# hv80_carrier.net
KiCad netlist of a schematic drawn in EAGLE
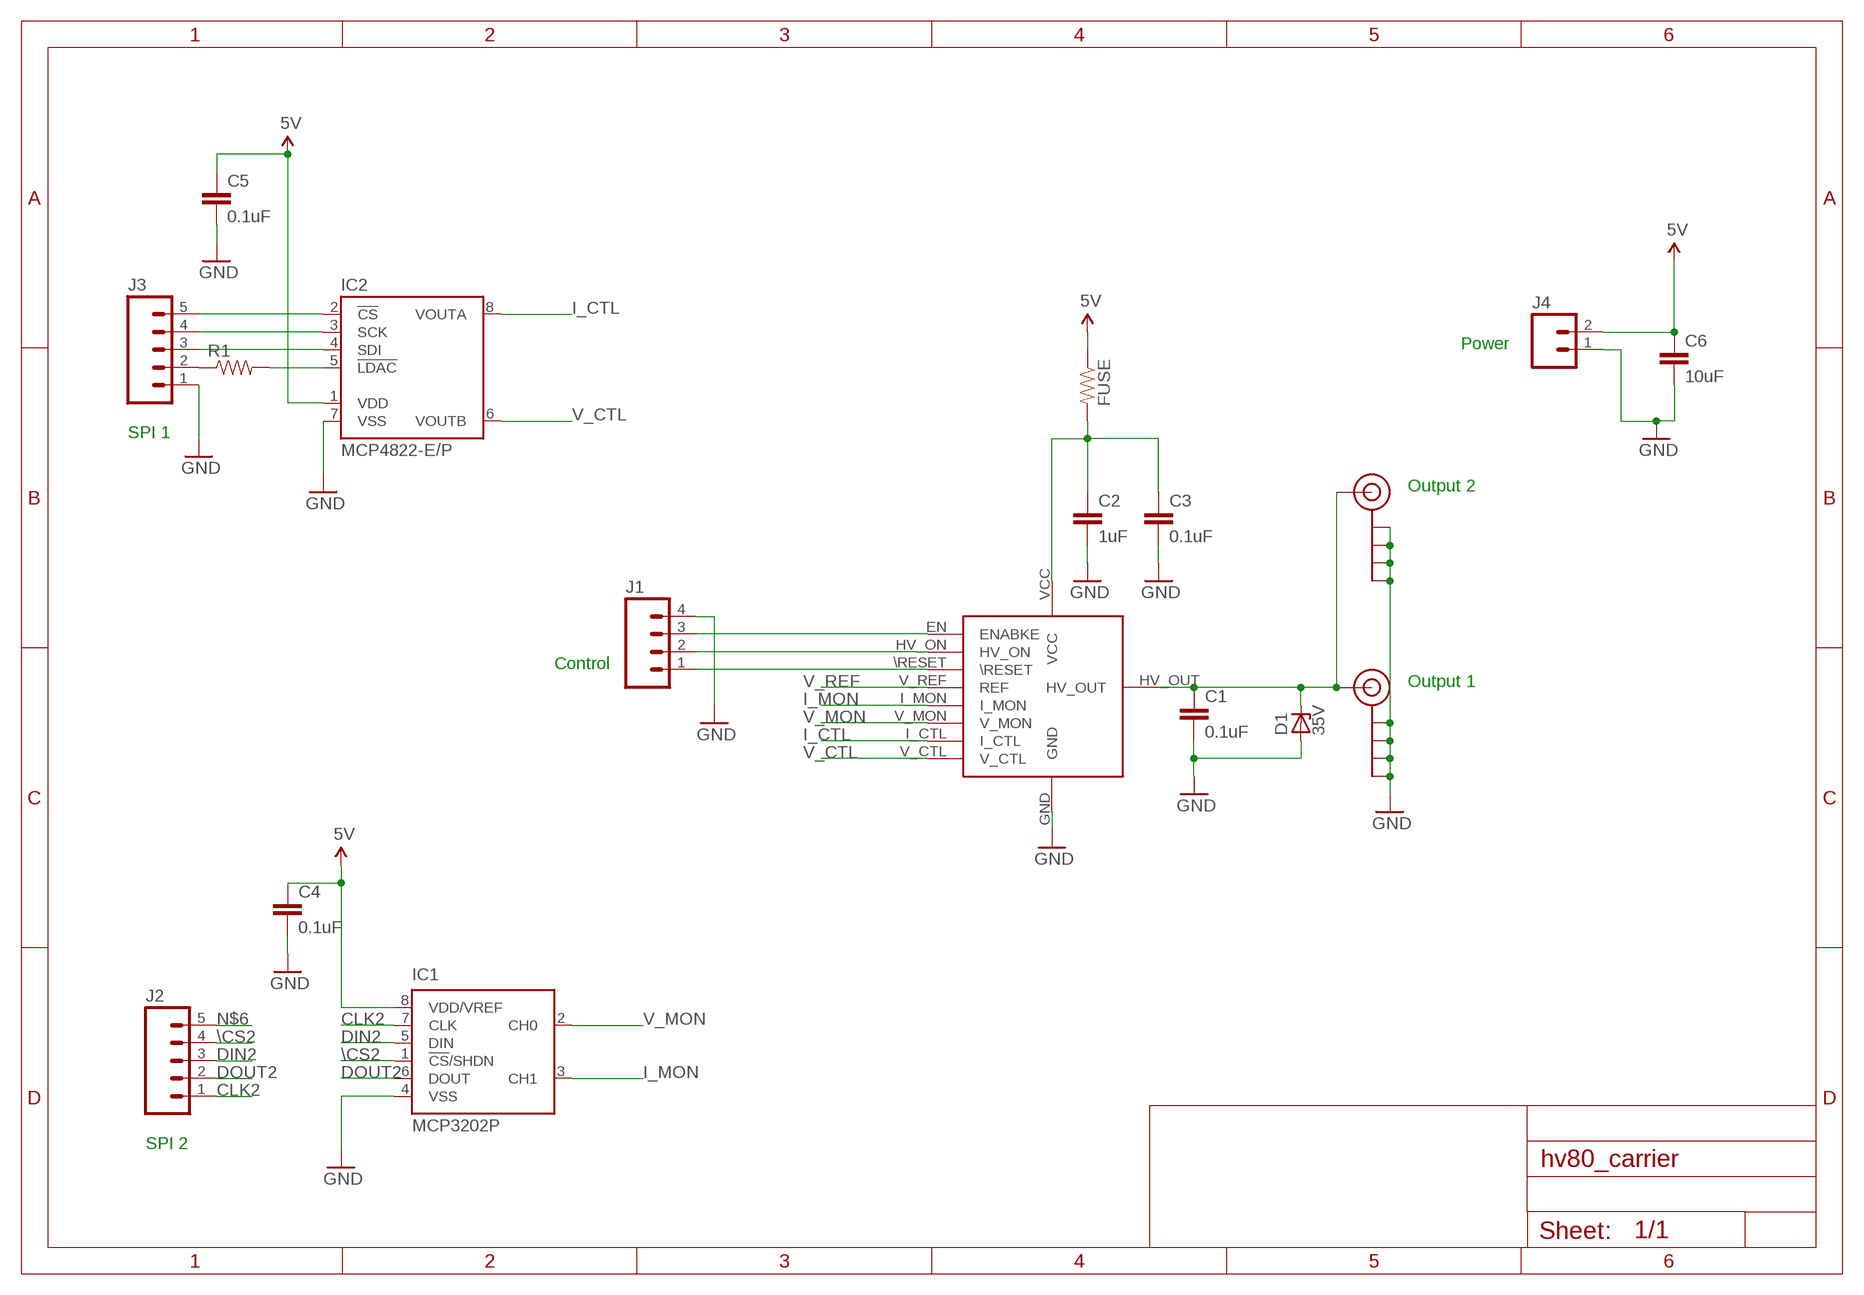
[diagram p0: schematic, sheet 1]

(export (version "E")
  (design (tool "Eeschema 10.0.6"))
  (components
    (comp (ref "C1")
      (value "0.1uF")
      (footprint "eagle-import:1206")
      (libsource (lib "eagle-import") (part "CAP1206"))
    )
    (comp (ref "C2")
      (value "1uF")
      (footprint "eagle-import:1206")
      (libsource (lib "eagle-import") (part "CAP1206"))
    )
    (comp (ref "C3")
      (value "0.1uF")
      (footprint "eagle-import:1206")
      (libsource (lib "eagle-import") (part "CAP1206"))
    )
    (comp (ref "C4")
      (value "0.1uF")
      (footprint "eagle-import:1206")
      (libsource (lib "eagle-import") (part "CAP1206"))
    )
    (comp (ref "C5")
      (value "0.1uF")
      (footprint "eagle-import:1206")
      (libsource (lib "eagle-import") (part "CAP1206"))
    )
    (comp (ref "C6")
      (value "10uF")
      (footprint "eagle-import:1206")
      (libsource (lib "eagle-import") (part "CAP1206"))
    )
    (comp (ref "D1")
      (value "35V")
      (footprint "eagle-import:DO41Z10")
      (libsource (lib "eagle-import") (part "ZENER-DIODEDO41Z10"))
    )
    (comp (ref "FUSE")
      (value "RESISTORPTH-1/4W")
      (footprint "eagle-import:AXIAL-0.4")
      (libsource (lib "eagle-import") (part "RESISTORPTH-1/4W"))
    )
    (comp (ref "IC1")
      (value "MCP3202P")
      (footprint "eagle-import:DIL8")
      (fields (field (name "MF") "MICROCHIP") (field (name "MPN") "MCP3202-CI/P"))
      (libsource (lib "eagle-import") (part "MCP3202P"))
    )
    (comp (ref "IC2")
      (value "MCP4822-E/P")
      (footprint "eagle-import:DIL08")
      (libsource (lib "eagle-import") (part "MCP4822-E/P"))
    )
    (comp (ref "J$1")
      (value "SMA_EDGE")
      (footprint "eagle-import:SMA-EDGE")
      (libsource (lib "eagle-import") (part "SMA_EDGE"))
    )
    (comp (ref "J$2")
      (value "SMA_EDGE")
      (footprint "eagle-import:SMA-EDGE")
      (libsource (lib "eagle-import") (part "SMA_EDGE"))
    )
    (comp (ref "J1")
      (value "M04PTH")
      (footprint "eagle-import:1X04")
      (libsource (lib "eagle-import") (part "M04PTH"))
    )
    (comp (ref "J2")
      (value "M05PTH")
      (footprint "eagle-import:1X05")
      (libsource (lib "eagle-import") (part "M05PTH"))
    )
    (comp (ref "J3")
      (value "M05PTH")
      (footprint "eagle-import:1X05")
      (libsource (lib "eagle-import") (part "M05PTH"))
    )
    (comp (ref "J4")
      (value "M023.5MM")
      (footprint "eagle-import:SCREWTERMINAL-3.5MM-2")
      (libsource (lib "eagle-import") (part "M023.5MM"))
    )
    (comp (ref "R1")
      (value "RESISTORPTH-1/4W")
      (footprint "eagle-import:AXIAL-0.4")
      (libsource (lib "eagle-import") (part "RESISTORPTH-1/4W"))
    )
    (comp (ref "U$1")
      (value "HV80")
      (footprint "eagle-import:HV80")
      (libsource (lib "eagle-import") (part "HV80"))
    )
  )
  (nets
    (net (code "1") (name "/CLK2") (class "Default")
      (node (ref "IC1") (pin "7") (pinfunction "CLK_7") (pintype "input"))
      (node (ref "J2") (pin "1") (pinfunction "1_1") (pintype "passive"))
    )
    (net (code "2") (name "/DIN2") (class "Default")
      (node (ref "IC1") (pin "5") (pinfunction "DIN_5") (pintype "input"))
      (node (ref "J2") (pin "3") (pinfunction "3_3") (pintype "passive"))
    )
    (net (code "3") (name "/DOUT2") (class "Default")
      (node (ref "IC1") (pin "6") (pinfunction "DOUT_6") (pintype "input"))
      (node (ref "J2") (pin "2") (pinfunction "2_2") (pintype "passive"))
    )
    (net (code "4") (name "/I_CTL") (class "Default")
      (node (ref "IC2") (pin "8") (pinfunction "VOUTA_8") (pintype "output"))
      (node (ref "U$1") (pin "I_CTL") (pinfunction "I_CTL_I_CTL") (pintype "bidirectional"))
    )
    (net (code "5") (name "/I_MON") (class "Default")
      (node (ref "IC1") (pin "3") (pinfunction "CH1_3") (pintype "input"))
      (node (ref "U$1") (pin "I_MON") (pinfunction "I_MON_I_MON") (pintype "bidirectional"))
    )
    (net (code "6") (name "/N$6") (class "Default")
      (node (ref "J2") (pin "5") (pinfunction "5_5") (pintype "passive"))
    )
    (net (code "7") (name "/V_CTL") (class "Default")
      (node (ref "IC2") (pin "6") (pinfunction "VOUTB_6") (pintype "output"))
      (node (ref "U$1") (pin "V_CTL") (pinfunction "V_CTL_V_CTL") (pintype "bidirectional"))
    )
    (net (code "8") (name "/V_MON") (class "Default")
      (node (ref "IC1") (pin "2") (pinfunction "CH0_2") (pintype "input"))
      (node (ref "U$1") (pin "V_MON") (pinfunction "V_MON_V_MON") (pintype "bidirectional"))
    )
    (net (code "9") (name "/V_REF") (class "Default")
      (node (ref "U$1") (pin "V_REF") (pinfunction "REF_V_REF") (pintype "bidirectional"))
    )
    (net (code "10") (name "/\\CS2") (class "Default")
      (node (ref "IC1") (pin "1") (pinfunction "~{CS}/SHDN_1") (pintype "input"))
      (node (ref "J2") (pin "4") (pinfunction "4_4") (pintype "passive"))
    )
    (net (code "11") (name "5V") (class "Default")
      (node (ref "C4") (pin "1") (pinfunction "1_1") (pintype "passive"))
      (node (ref "C5") (pin "1") (pinfunction "1_1") (pintype "passive"))
      (node (ref "C6") (pin "1") (pinfunction "1_1") (pintype "passive"))
      (node (ref "FUSE") (pin "P$1") (pinfunction "1_P$1") (pintype "passive"))
      (node (ref "IC1") (pin "8") (pinfunction "VDD/VREF_8") (pintype "input"))
      (node (ref "IC2") (pin "1") (pinfunction "VDD_1") (pintype "power_in"))
      (node (ref "J4") (pin "2") (pinfunction "2_2") (pintype "passive"))
    )
    (net (code "12") (name "GND") (class "Default")
      (node (ref "C1") (pin "2") (pinfunction "2_2") (pintype "passive"))
      (node (ref "C2") (pin "2") (pinfunction "2_2") (pintype "passive"))
      (node (ref "C3") (pin "2") (pinfunction "2_2") (pintype "passive"))
      (node (ref "C4") (pin "2") (pinfunction "2_2") (pintype "passive"))
      (node (ref "C5") (pin "2") (pinfunction "2_2") (pintype "passive"))
      (node (ref "C6") (pin "2") (pinfunction "2_2") (pintype "passive"))
      (node (ref "D1") (pin "A") (pinfunction "A_A") (pintype "passive"))
      (node (ref "IC1") (pin "4") (pinfunction "VSS_4") (pintype "input"))
      (node (ref "IC2") (pin "7") (pinfunction "VSS_7") (pintype "power_in"))
      (node (ref "J$1") (pin "GND@0") (pinfunction "GND_GND@0") (pintype "bidirectional"))
      (node (ref "J$1") (pin "GND@1") (pinfunction "GND_GND@1") (pintype "bidirectional"))
      (node (ref "J$1") (pin "GND@2") (pinfunction "GND_GND@2") (pintype "bidirectional"))
      (node (ref "J$1") (pin "GND@3") (pinfunction "GND_GND@3") (pintype "bidirectional"))
      (node (ref "J$2") (pin "GND@0") (pinfunction "GND_GND@0") (pintype "bidirectional"))
      (node (ref "J$2") (pin "GND@1") (pinfunction "GND_GND@1") (pintype "bidirectional"))
      (node (ref "J$2") (pin "GND@2") (pinfunction "GND_GND@2") (pintype "bidirectional"))
      (node (ref "J$2") (pin "GND@3") (pinfunction "GND_GND@3") (pintype "bidirectional"))
      (node (ref "J1") (pin "4") (pinfunction "4_4") (pintype "passive"))
      (node (ref "J3") (pin "1") (pinfunction "1_1") (pintype "passive"))
      (node (ref "J4") (pin "1") (pinfunction "1_1") (pintype "passive"))
      (node (ref "U$1") (pin "GND") (pinfunction "GND_GND") (pintype "bidirectional"))
    )
    (net (code "13") (name "Net-(FUSE-2)") (class "Default")
      (node (ref "C2") (pin "1") (pinfunction "1_1") (pintype "passive"))
      (node (ref "C3") (pin "1") (pinfunction "1_1") (pintype "passive"))
      (node (ref "FUSE") (pin "P$2") (pinfunction "2_P$2") (pintype "passive"))
      (node (ref "U$1") (pin "VCC") (pinfunction "VCC_VCC") (pintype "bidirectional"))
    )
    (net (code "14") (name "Net-(IC2-SCK)") (class "Default")
      (node (ref "IC2") (pin "3") (pinfunction "SCK_3") (pintype "input"))
      (node (ref "J3") (pin "4") (pinfunction "4_4") (pintype "passive"))
    )
    (net (code "15") (name "Net-(IC2-SDI)") (class "Default")
      (node (ref "IC2") (pin "4") (pinfunction "SDI_4") (pintype "input"))
      (node (ref "J3") (pin "3") (pinfunction "3_3") (pintype "passive"))
    )
    (net (code "16") (name "Net-(IC2-~{CS})") (class "Default")
      (node (ref "IC2") (pin "2") (pinfunction "~{CS}_2") (pintype "input"))
      (node (ref "J3") (pin "5") (pinfunction "5_5") (pintype "passive"))
    )
    (net (code "17") (name "Net-(IC2-~{LDAC})") (class "Default")
      (node (ref "IC2") (pin "5") (pinfunction "~{LDAC}_5") (pintype "input"))
      (node (ref "R1") (pin "P$2") (pinfunction "2_P$2") (pintype "passive"))
    )
    (net (code "18") (name "Net-(J$1-SIGNAL)") (class "Default")
      (node (ref "C1") (pin "1") (pinfunction "1_1") (pintype "passive"))
      (node (ref "D1") (pin "C") (pinfunction "C_C") (pintype "passive"))
      (node (ref "J$1") (pin "SIG") (pinfunction "SIGNAL_SIG") (pintype "bidirectional"))
      (node (ref "J$2") (pin "SIG") (pinfunction "SIGNAL_SIG") (pintype "bidirectional"))
      (node (ref "U$1") (pin "HV_OUT") (pinfunction "HV_OUT_HV_OUT") (pintype "bidirectional"))
    )
    (net (code "19") (name "Net-(J1-Pad1)") (class "Default")
      (node (ref "J1") (pin "1") (pinfunction "1_1") (pintype "passive"))
      (node (ref "U$1") (pin "\\RESET") (pinfunction "\\RESET_\\RESET") (pintype "bidirectional"))
    )
    (net (code "20") (name "Net-(J1-Pad2)") (class "Default")
      (node (ref "J1") (pin "2") (pinfunction "2_2") (pintype "passive"))
      (node (ref "U$1") (pin "HV_ON") (pinfunction "HV_ON_HV_ON") (pintype "bidirectional"))
    )
    (net (code "21") (name "Net-(R1-1)") (class "Default")
      (node (ref "J3") (pin "2") (pinfunction "2_2") (pintype "passive"))
      (node (ref "R1") (pin "P$1") (pinfunction "1_P$1") (pintype "passive"))
    )
    (net (code "22") (name "Net-(U$1-ENABKE)") (class "Default")
      (node (ref "J1") (pin "3") (pinfunction "3_3") (pintype "passive"))
      (node (ref "U$1") (pin "EN") (pinfunction "ENABKE_EN") (pintype "bidirectional"))
    )
  )
)
